# LVDS.net
KiCad netlist of a schematic drawn in Altium Designer
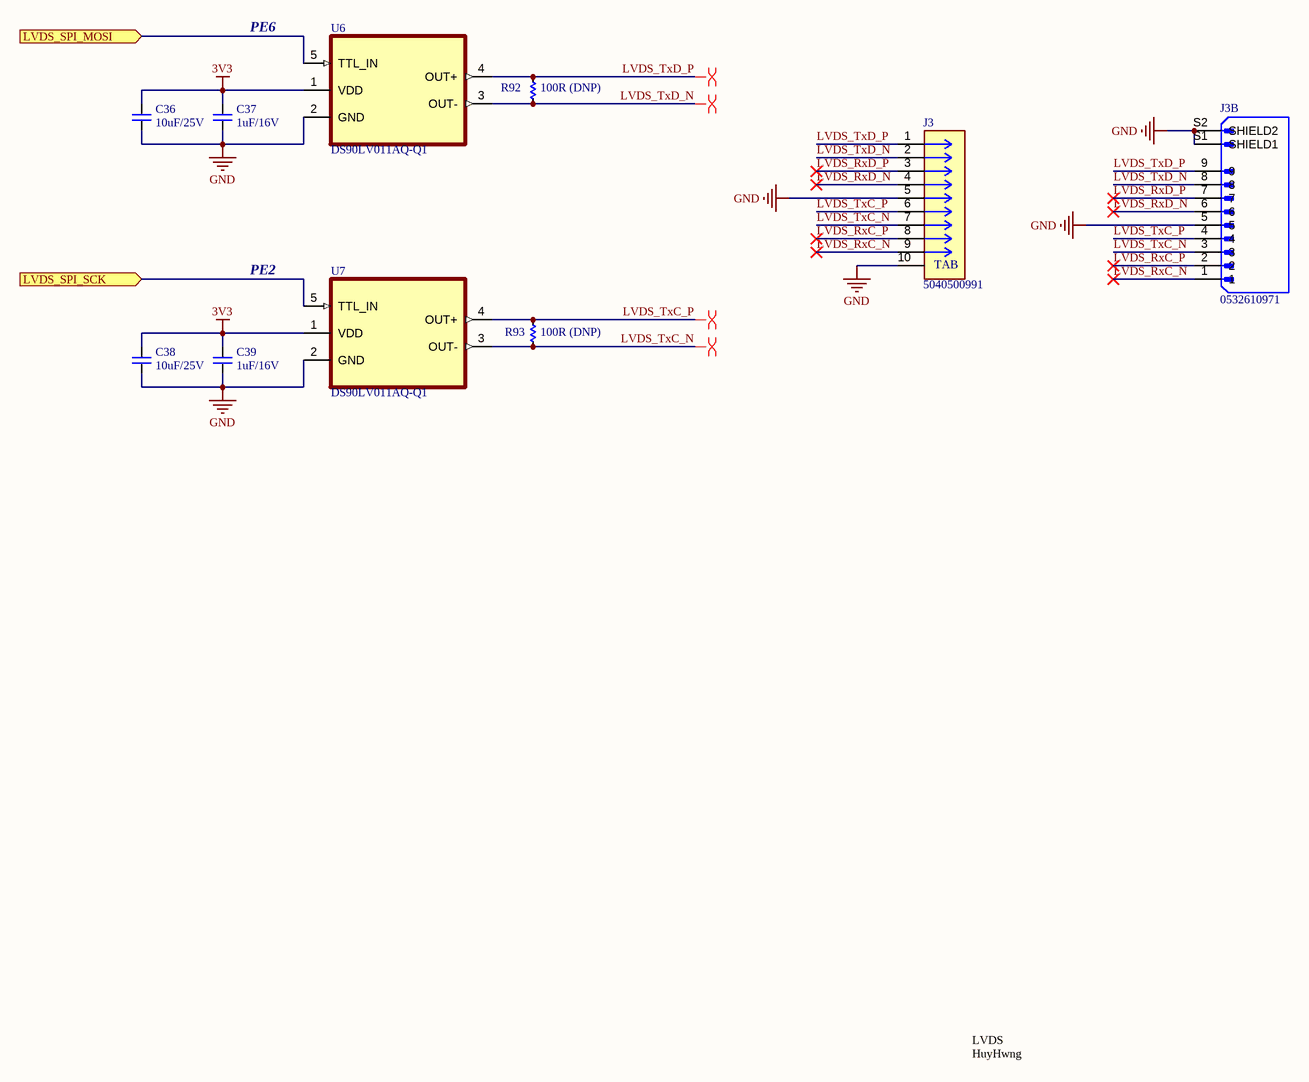
[diagram p0: LVDS.SchDoc]

(export (version "E")
  (design (tool "Eeschema 10.0.6"))
  (components
    (comp (ref "C36")
      (value "10uF/25V")
      (footprint "CAP_C_1608X80")
      (description "CAP_Chip")
      (libsource (lib "LABLIB") (part "CAP_SMD"))
    )
    (comp (ref "C37")
      (value "1uF/16V")
      (footprint "CAP_C_1608X80")
      (description "CAP_Chip")
      (libsource (lib "LABLIB") (part "CAP_SMD"))
    )
    (comp (ref "C38")
      (value "10uF/25V")
      (footprint "CAP_C_1608X80")
      (description "CAP_Chip")
      (libsource (lib "LABLIB") (part "CAP_SMD"))
    )
    (comp (ref "C39")
      (value "1uF/16V")
      (footprint "CAP_C_1608X80")
      (description "CAP_Chip")
      (libsource (lib "LABLIB") (part "CAP_SMD"))
    )
    (comp (ref "J3")
      (value "5040500991")
      (footprint "5040500991")
      (description "Connector Header Surface Mount, Right Angle 9 position 0.059\" (1.50mm)")
      (libsource (lib "COMM_SCHLIB") (part "5040500991"))
    )
    (comp (ref "J3B")
      (value "0532610971")
      (footprint "0532610971")
      (description "CONN HEADER SMD R/A 9POS 1.25MM")
      (libsource (lib "COMM_SCHLIB") (part "CONN_SMD_09"))
    )
    (comp (ref "R92")
      (value "100R (DNP)")
      (footprint "RES_C_1608X60")
      (description "RES")
      (libsource (lib "LABLIB") (part "_RES_B_2"))
    )
    (comp (ref "R93")
      (value "100R (DNP)")
      (footprint "RES_C_1608X60")
      (description "RES")
      (libsource (lib "LABLIB") (part "_RES_B_2"))
    )
    (comp (ref "U6")
      (value "DS90LV011AQ-Q1")
      (footprint "DS90LV011AQ-Q1")
      (description "Automotive LVDS Differential Driver")
      (libsource (lib "COMM_SCHLIB") (part "DS90LV011AQ-Q1"))
    )
    (comp (ref "U7")
      (value "DS90LV011AQ-Q1")
      (footprint "DS90LV011AQ-Q1")
      (description "Automotive LVDS Differential Driver")
      (libsource (lib "COMM_SCHLIB") (part "DS90LV011AQ-Q1"))
    )
  )
  (nets
    (net (code "1") (name "/LVDS_RxC_N") (class "Default")
      (node (ref "J3") (pin "9") (pinfunction "9_9") (pintype "passive"))
      (node (ref "J3B") (pin "1") (pinfunction "1_1") (pintype "passive"))
    )
    (net (code "2") (name "/LVDS_RxC_P") (class "Default")
      (node (ref "J3") (pin "8") (pinfunction "8_8") (pintype "passive"))
      (node (ref "J3B") (pin "2") (pinfunction "2_2") (pintype "passive"))
    )
    (net (code "3") (name "/LVDS_RxD_N") (class "Default")
      (node (ref "J3") (pin "4") (pinfunction "4_4") (pintype "passive"))
      (node (ref "J3B") (pin "6") (pinfunction "6_6") (pintype "passive"))
    )
    (net (code "4") (name "/LVDS_RxD_P") (class "Default")
      (node (ref "J3") (pin "3") (pinfunction "3_3") (pintype "passive"))
      (node (ref "J3B") (pin "7") (pinfunction "7_7") (pintype "passive"))
    )
    (net (code "5") (name "/LVDS_SPI_MOSI") (class "Default")
      (node (ref "U6") (pin "5") (pinfunction "TTL_IN_5") (pintype "input"))
    )
    (net (code "6") (name "/LVDS_SPI_SCK") (class "Default")
      (node (ref "U7") (pin "5") (pinfunction "TTL_IN_5") (pintype "input"))
    )
    (net (code "7") (name "/LVDS_TxC_N") (class "Default")
      (node (ref "J3") (pin "7") (pinfunction "7_7") (pintype "passive"))
      (node (ref "J3B") (pin "3") (pinfunction "3_3") (pintype "passive"))
      (node (ref "R93") (pin "1") (pinfunction "1_1") (pintype "passive"))
      (node (ref "U7") (pin "3") (pinfunction "OUT-_3") (pintype "output"))
    )
    (net (code "8") (name "/LVDS_TxC_P") (class "Default")
      (node (ref "J3") (pin "6") (pinfunction "6_6") (pintype "passive"))
      (node (ref "J3B") (pin "4") (pinfunction "4_4") (pintype "passive"))
      (node (ref "R93") (pin "2") (pinfunction "2_2") (pintype "passive"))
      (node (ref "U7") (pin "4") (pinfunction "OUT+_4") (pintype "output"))
    )
    (net (code "9") (name "/LVDS_TxD_N") (class "Default")
      (node (ref "J3") (pin "2") (pinfunction "2_2") (pintype "passive"))
      (node (ref "J3B") (pin "8") (pinfunction "8_8") (pintype "passive"))
      (node (ref "R92") (pin "1") (pinfunction "1_1") (pintype "passive"))
      (node (ref "U6") (pin "3") (pinfunction "OUT-_3") (pintype "output"))
    )
    (net (code "10") (name "/LVDS_TxD_P") (class "Default")
      (node (ref "J3") (pin "1") (pinfunction "1_1") (pintype "passive"))
      (node (ref "J3B") (pin "9") (pinfunction "9_9") (pintype "passive"))
      (node (ref "R92") (pin "2") (pinfunction "2_2") (pintype "passive"))
      (node (ref "U6") (pin "4") (pinfunction "OUT+_4") (pintype "output"))
    )
    (net (code "11") (name "3V3") (class "Default")
      (node (ref "C36") (pin "2") (pinfunction "2_2") (pintype "passive"))
      (node (ref "C37") (pin "2") (pinfunction "2_2") (pintype "passive"))
      (node (ref "C38") (pin "2") (pinfunction "2_2") (pintype "passive"))
      (node (ref "C39") (pin "2") (pinfunction "2_2") (pintype "passive"))
      (node (ref "U6") (pin "1") (pinfunction "VDD_1") (pintype "power_in"))
      (node (ref "U7") (pin "1") (pinfunction "VDD_1") (pintype "power_in"))
    )
    (net (code "12") (name "GND") (class "Default")
      (node (ref "C36") (pin "1") (pinfunction "1_1") (pintype "passive"))
      (node (ref "C37") (pin "1") (pinfunction "1_1") (pintype "passive"))
      (node (ref "C38") (pin "1") (pinfunction "1_1") (pintype "passive"))
      (node (ref "C39") (pin "1") (pinfunction "1_1") (pintype "passive"))
      (node (ref "J3") (pin "10") (pinfunction "10_10") (pintype "passive"))
      (node (ref "J3") (pin "5") (pinfunction "5_5") (pintype "passive"))
      (node (ref "J3B") (pin "5") (pinfunction "5_5") (pintype "passive"))
      (node (ref "J3B") (pin "S1") (pinfunction "SHIELD1_S1") (pintype "passive"))
      (node (ref "J3B") (pin "S2") (pinfunction "SHIELD2_S2") (pintype "passive"))
      (node (ref "U6") (pin "2") (pinfunction "GND_2") (pintype "power_in"))
      (node (ref "U7") (pin "2") (pinfunction "GND_2") (pintype "power_in"))
    )
  )
)
